# ServoLevelShifter.net
KiCad netlist of a schematic drawn in Altium Designer
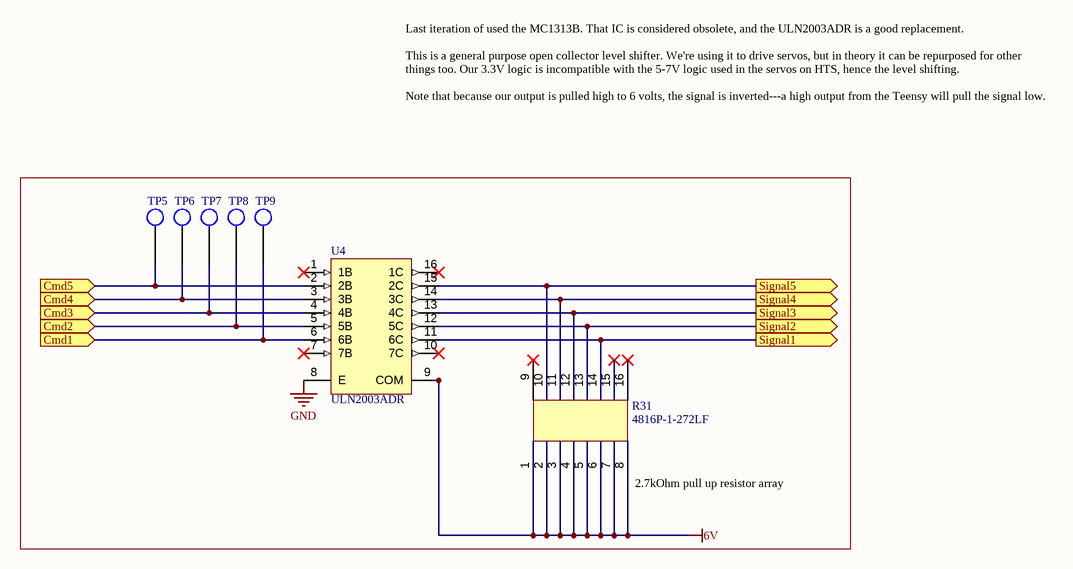
[diagram p0: ServoLevelShifter.SchDoc]

(export (version "E")
  (design (tool "Eeschema 10.0.6"))
  (components
    (comp (ref "R31")
      (value "4816P-1-272LF")
      (footprint "Miscellaneous Devices:SOIC16_N")
      (libsource (lib "4816P-1-272LF") (part "4816P-1-272LF"))
    )
    (comp (ref "TP5")
      (value "BURPG_TestPoint1")
      (footprint "BURPG_TestPoint1")
      (libsource (lib "BURPG_generic") (part "BURPG_TestPoint1"))
    )
    (comp (ref "TP6")
      (value "BURPG_TestPoint1")
      (footprint "BURPG_TestPoint1")
      (libsource (lib "BURPG_generic") (part "BURPG_TestPoint1"))
    )
    (comp (ref "TP7")
      (value "BURPG_TestPoint1")
      (footprint "BURPG_TestPoint1")
      (libsource (lib "BURPG_generic") (part "BURPG_TestPoint1"))
    )
    (comp (ref "TP8")
      (value "BURPG_TestPoint1")
      (footprint "BURPG_TestPoint1")
      (libsource (lib "BURPG_generic") (part "BURPG_TestPoint1"))
    )
    (comp (ref "TP9")
      (value "BURPG_TestPoint1")
      (footprint "BURPG_TestPoint1")
      (libsource (lib "BURPG_generic") (part "BURPG_TestPoint1"))
    )
    (comp (ref "U4")
      (value "ULN2003ADR")
      (footprint "D0016A_M")
      (fields (field (name "MANUFACTURER") "TexasInstruments"))
      (libsource (lib "Altium Content Vault") (part "TI-ULX200X-D-16"))
    )
  )
  (nets
    (net (code "1") (name "/Cmd1") (class "Default")
      (node (ref "TP9") (pin "1") (pinfunction "1_1") (pintype "passive"))
      (node (ref "U4") (pin "6") (pinfunction "6B_6") (pintype "input"))
    )
    (net (code "2") (name "/Cmd2") (class "Default")
      (node (ref "TP8") (pin "1") (pinfunction "1_1") (pintype "passive"))
      (node (ref "U4") (pin "5") (pinfunction "5B_5") (pintype "input"))
    )
    (net (code "3") (name "/Cmd3") (class "Default")
      (node (ref "TP7") (pin "1") (pinfunction "1_1") (pintype "passive"))
      (node (ref "U4") (pin "4") (pinfunction "4B_4") (pintype "input"))
    )
    (net (code "4") (name "/Cmd4") (class "Default")
      (node (ref "TP6") (pin "1") (pinfunction "1_1") (pintype "passive"))
      (node (ref "U4") (pin "3") (pinfunction "3B_3") (pintype "input"))
    )
    (net (code "5") (name "/Cmd5") (class "Default")
      (node (ref "TP5") (pin "1") (pinfunction "1_1") (pintype "passive"))
      (node (ref "U4") (pin "2") (pinfunction "2B_2") (pintype "input"))
    )
    (net (code "6") (name "/Signal1") (class "Default")
      (node (ref "R31") (pin "14") (pinfunction "14_14") (pintype "passive"))
      (node (ref "U4") (pin "11") (pinfunction "6C_11") (pintype "output"))
    )
    (net (code "7") (name "/Signal2") (class "Default")
      (node (ref "R31") (pin "13") (pinfunction "13_13") (pintype "passive"))
      (node (ref "U4") (pin "12") (pinfunction "5C_12") (pintype "output"))
    )
    (net (code "8") (name "/Signal3") (class "Default")
      (node (ref "R31") (pin "12") (pinfunction "12_12") (pintype "passive"))
      (node (ref "U4") (pin "13") (pinfunction "4C_13") (pintype "output"))
    )
    (net (code "9") (name "/Signal4") (class "Default")
      (node (ref "R31") (pin "11") (pinfunction "11_11") (pintype "passive"))
      (node (ref "U4") (pin "14") (pinfunction "3C_14") (pintype "output"))
    )
    (net (code "10") (name "/Signal5") (class "Default")
      (node (ref "R31") (pin "10") (pinfunction "10_10") (pintype "passive"))
      (node (ref "U4") (pin "15") (pinfunction "2C_15") (pintype "output"))
    )
    (net (code "11") (name "6V") (class "Default")
      (node (ref "R31") (pin "1") (pinfunction "1_1") (pintype "passive"))
      (node (ref "R31") (pin "2") (pinfunction "2_2") (pintype "passive"))
      (node (ref "R31") (pin "3") (pinfunction "3_3") (pintype "passive"))
      (node (ref "R31") (pin "4") (pinfunction "4_4") (pintype "passive"))
      (node (ref "R31") (pin "5") (pinfunction "5_5") (pintype "passive"))
      (node (ref "R31") (pin "6") (pinfunction "6_6") (pintype "passive"))
      (node (ref "R31") (pin "7") (pinfunction "7_7") (pintype "passive"))
      (node (ref "R31") (pin "8") (pinfunction "8_8") (pintype "passive"))
      (node (ref "U4") (pin "9") (pinfunction "COM_9") (pintype "passive"))
    )
    (net (code "12") (name "GND") (class "Default")
      (node (ref "U4") (pin "8") (pinfunction "E_8") (pintype "passive"))
    )
    (net (code "13") (name "unconnected-(R31-Pad9)") (class "Default")
      (node (ref "R31") (pin "9") (pinfunction "9_9") (pintype "passive"))
    )
    (net (code "14") (name "unconnected-(R31-Pad15)") (class "Default")
      (node (ref "R31") (pin "15") (pinfunction "15_15") (pintype "passive+no_connect"))
    )
    (net (code "15") (name "unconnected-(R31-Pad16)") (class "Default")
      (node (ref "R31") (pin "16") (pinfunction "16_16") (pintype "passive+no_connect"))
    )
    (net (code "16") (name "unconnected-(U4-1B-Pad1)") (class "Default")
      (node (ref "U4") (pin "1") (pinfunction "1B_1") (pintype "input+no_connect"))
    )
    (net (code "17") (name "unconnected-(U4-1C-Pad16)") (class "Default")
      (node (ref "U4") (pin "16") (pinfunction "1C_16") (pintype "output+no_connect"))
    )
    (net (code "18") (name "unconnected-(U4-7B-Pad7)") (class "Default")
      (node (ref "U4") (pin "7") (pinfunction "7B_7") (pintype "input+no_connect"))
    )
    (net (code "19") (name "unconnected-(U4-7C-Pad10)") (class "Default")
      (node (ref "U4") (pin "10") (pinfunction "7C_10") (pintype "output+no_connect"))
    )
  )
)
